# 5v_and_Filters.net
KiCad netlist of a schematic drawn in Altium Designer
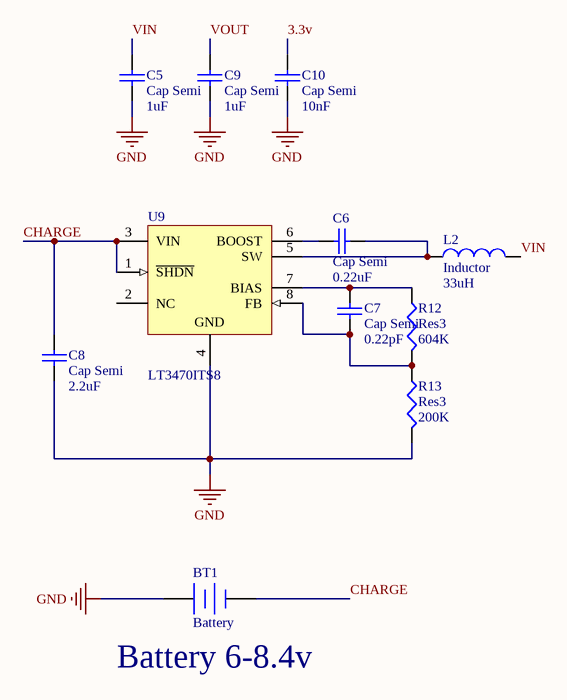
[diagram p0: 5v and Filters.SchDoc]

(export (version "E")
  (design (tool "Eeschema 10.0.6"))
  (components
    (comp (ref "BT1")
      (value "Battery")
      (footprint "BAT-2")
      (description "Multicell Battery")
      (fields (field (name "PUBLISHER") "Altium Limited"))
      (libsource (lib "Miscellaneous Devices") (part "Battery"))
    )
    (comp (ref "C5")
      (value "Cap Semi")
      (footprint "C1206")
      (description "Capacitor (Semiconductor SIM Model)")
      (fields (field (name "ALTIUM_VALUE") "1uF") (field (name "PUBLISHER") "Altium Limited"))
      (libsource (lib "Miscellaneous Devices") (part "Cap Semi"))
    )
    (comp (ref "C6")
      (value "Cap Semi")
      (footprint "C1206")
      (description "Capacitor (Semiconductor SIM Model)")
      (fields (field (name "ALTIUM_VALUE") "0.22uF") (field (name "PUBLISHER") "Altium Limited"))
      (libsource (lib "Miscellaneous Devices") (part "Cap Semi"))
    )
    (comp (ref "C7")
      (value "Cap Semi")
      (footprint "C1206")
      (description "Capacitor (Semiconductor SIM Model)")
      (fields (field (name "ALTIUM_VALUE") "0.22pF") (field (name "PUBLISHER") "Altium Limited"))
      (libsource (lib "Miscellaneous Devices") (part "Cap Semi"))
    )
    (comp (ref "C8")
      (value "Cap Semi")
      (footprint "C1206")
      (description "Capacitor (Semiconductor SIM Model)")
      (fields (field (name "ALTIUM_VALUE") "2.2uF") (field (name "PUBLISHER") "Altium Limited"))
      (libsource (lib "Miscellaneous Devices") (part "Cap Semi"))
    )
    (comp (ref "C9")
      (value "Cap Semi")
      (footprint "C1206")
      (description "Capacitor (Semiconductor SIM Model)")
      (fields (field (name "ALTIUM_VALUE") "1uF") (field (name "PUBLISHER") "Altium Limited"))
      (libsource (lib "Miscellaneous Devices") (part "Cap Semi"))
    )
    (comp (ref "C10")
      (value "Cap Semi")
      (footprint "C1206")
      (description "Capacitor (Semiconductor SIM Model)")
      (fields (field (name "ALTIUM_VALUE") "10nF") (field (name "PUBLISHER") "Altium Limited"))
      (libsource (lib "Miscellaneous Devices") (part "Cap Semi"))
    )
    (comp (ref "L2")
      (value "Inductor")
      (footprint "0402-A")
      (fields (field (name "ALTIUM_VALUE") "33uH") (field (name "PUBLISHER") "Altium Limited"))
      (libsource (lib "Miscellaneous Devices") (part "Inductor"))
    )
    (comp (ref "R12")
      (value "Res3")
      (footprint "J1-0603")
      (description "Resistor")
      (fields (field (name "ALTIUM_VALUE") "604K") (field (name "PUBLISHER") "Altium Limited"))
      (libsource (lib "Miscellaneous Devices") (part "Res3"))
    )
    (comp (ref "R13")
      (value "Res3")
      (footprint "J1-0603")
      (description "Resistor")
      (fields (field (name "ALTIUM_VALUE") "200K") (field (name "PUBLISHER") "Altium Limited"))
      (libsource (lib "Miscellaneous Devices") (part "Res3"))
    )
    (comp (ref "U9")
      (value "LT3470ITS8")
      (footprint "LT-TS8-8-TSOT-23_V")
      (fields (field (name "MANUFACTURER") "Linear Technology"))
      (libsource (lib "Altium Content Vault") (part "LT-LT3470-TS8-8"))
    )
  )
  (nets
    (net (code "1") (name "/3.3v") (class "Default")
      (node (ref "C10") (pin "2") (pinfunction "2_2") (pintype "passive"))
    )
    (net (code "2") (name "/CHARGE") (class "Default")
      (node (ref "BT1") (pin "2") (pinfunction "-_2") (pintype "passive"))
      (node (ref "C8") (pin "1") (pinfunction "1_1") (pintype "passive"))
      (node (ref "U9") (pin "1") (pinfunction "~{SHDN}_1") (pintype "input"))
      (node (ref "U9") (pin "3") (pinfunction "VIN_3") (pintype "power_in"))
    )
    (net (code "3") (name "/VIN") (class "Default")
      (node (ref "C5") (pin "2") (pinfunction "2_2") (pintype "passive"))
      (node (ref "L2") (pin "2") (pinfunction "2_2") (pintype "passive"))
    )
    (net (code "4") (name "/VOUT") (class "Default")
      (node (ref "C9") (pin "2") (pinfunction "2_2") (pintype "passive"))
    )
    (net (code "5") (name "GND") (class "Default")
      (node (ref "BT1") (pin "1") (pinfunction "+_1") (pintype "passive"))
      (node (ref "C10") (pin "1") (pinfunction "1_1") (pintype "passive"))
      (node (ref "C5") (pin "1") (pinfunction "1_1") (pintype "passive"))
      (node (ref "C8") (pin "2") (pinfunction "2_2") (pintype "passive"))
      (node (ref "C9") (pin "1") (pinfunction "1_1") (pintype "passive"))
      (node (ref "R13") (pin "2") (pinfunction "2_2") (pintype "passive"))
      (node (ref "U9") (pin "4") (pinfunction "GND_4") (pintype "power_in"))
    )
    (net (code "6") (name "Net-(U9-BIAS)") (class "Default")
      (node (ref "C7") (pin "1") (pinfunction "1_1") (pintype "passive"))
      (node (ref "R12") (pin "1") (pinfunction "1_1") (pintype "passive"))
      (node (ref "U9") (pin "7") (pinfunction "BIAS_7") (pintype "power_in"))
    )
    (net (code "7") (name "Net-(U9-BOOST)") (class "Default")
      (node (ref "C6") (pin "1") (pinfunction "1_1") (pintype "passive"))
      (node (ref "U9") (pin "6") (pinfunction "BOOST_6") (pintype "passive"))
    )
    (net (code "8") (name "Net-(U9-FB)") (class "Default")
      (node (ref "C7") (pin "2") (pinfunction "2_2") (pintype "passive"))
      (node (ref "R12") (pin "2") (pinfunction "2_2") (pintype "passive"))
      (node (ref "R13") (pin "1") (pinfunction "1_1") (pintype "passive"))
      (node (ref "U9") (pin "8") (pinfunction "FB_8") (pintype "input"))
    )
    (net (code "9") (name "Net-(U9-SW)") (class "Default")
      (node (ref "C6") (pin "2") (pinfunction "2_2") (pintype "passive"))
      (node (ref "L2") (pin "1") (pinfunction "1_1") (pintype "passive"))
      (node (ref "U9") (pin "5") (pinfunction "SW_5") (pintype "power_in"))
    )
    (net (code "10") (name "unconnected-(U9-NC-Pad2)") (class "Default")
      (node (ref "U9") (pin "2") (pinfunction "NC_2") (pintype "passive"))
    )
  )
)
